# SchematicArtiom_fsch_v13.net
KiCad netlist of a schematic drawn in EAGLE
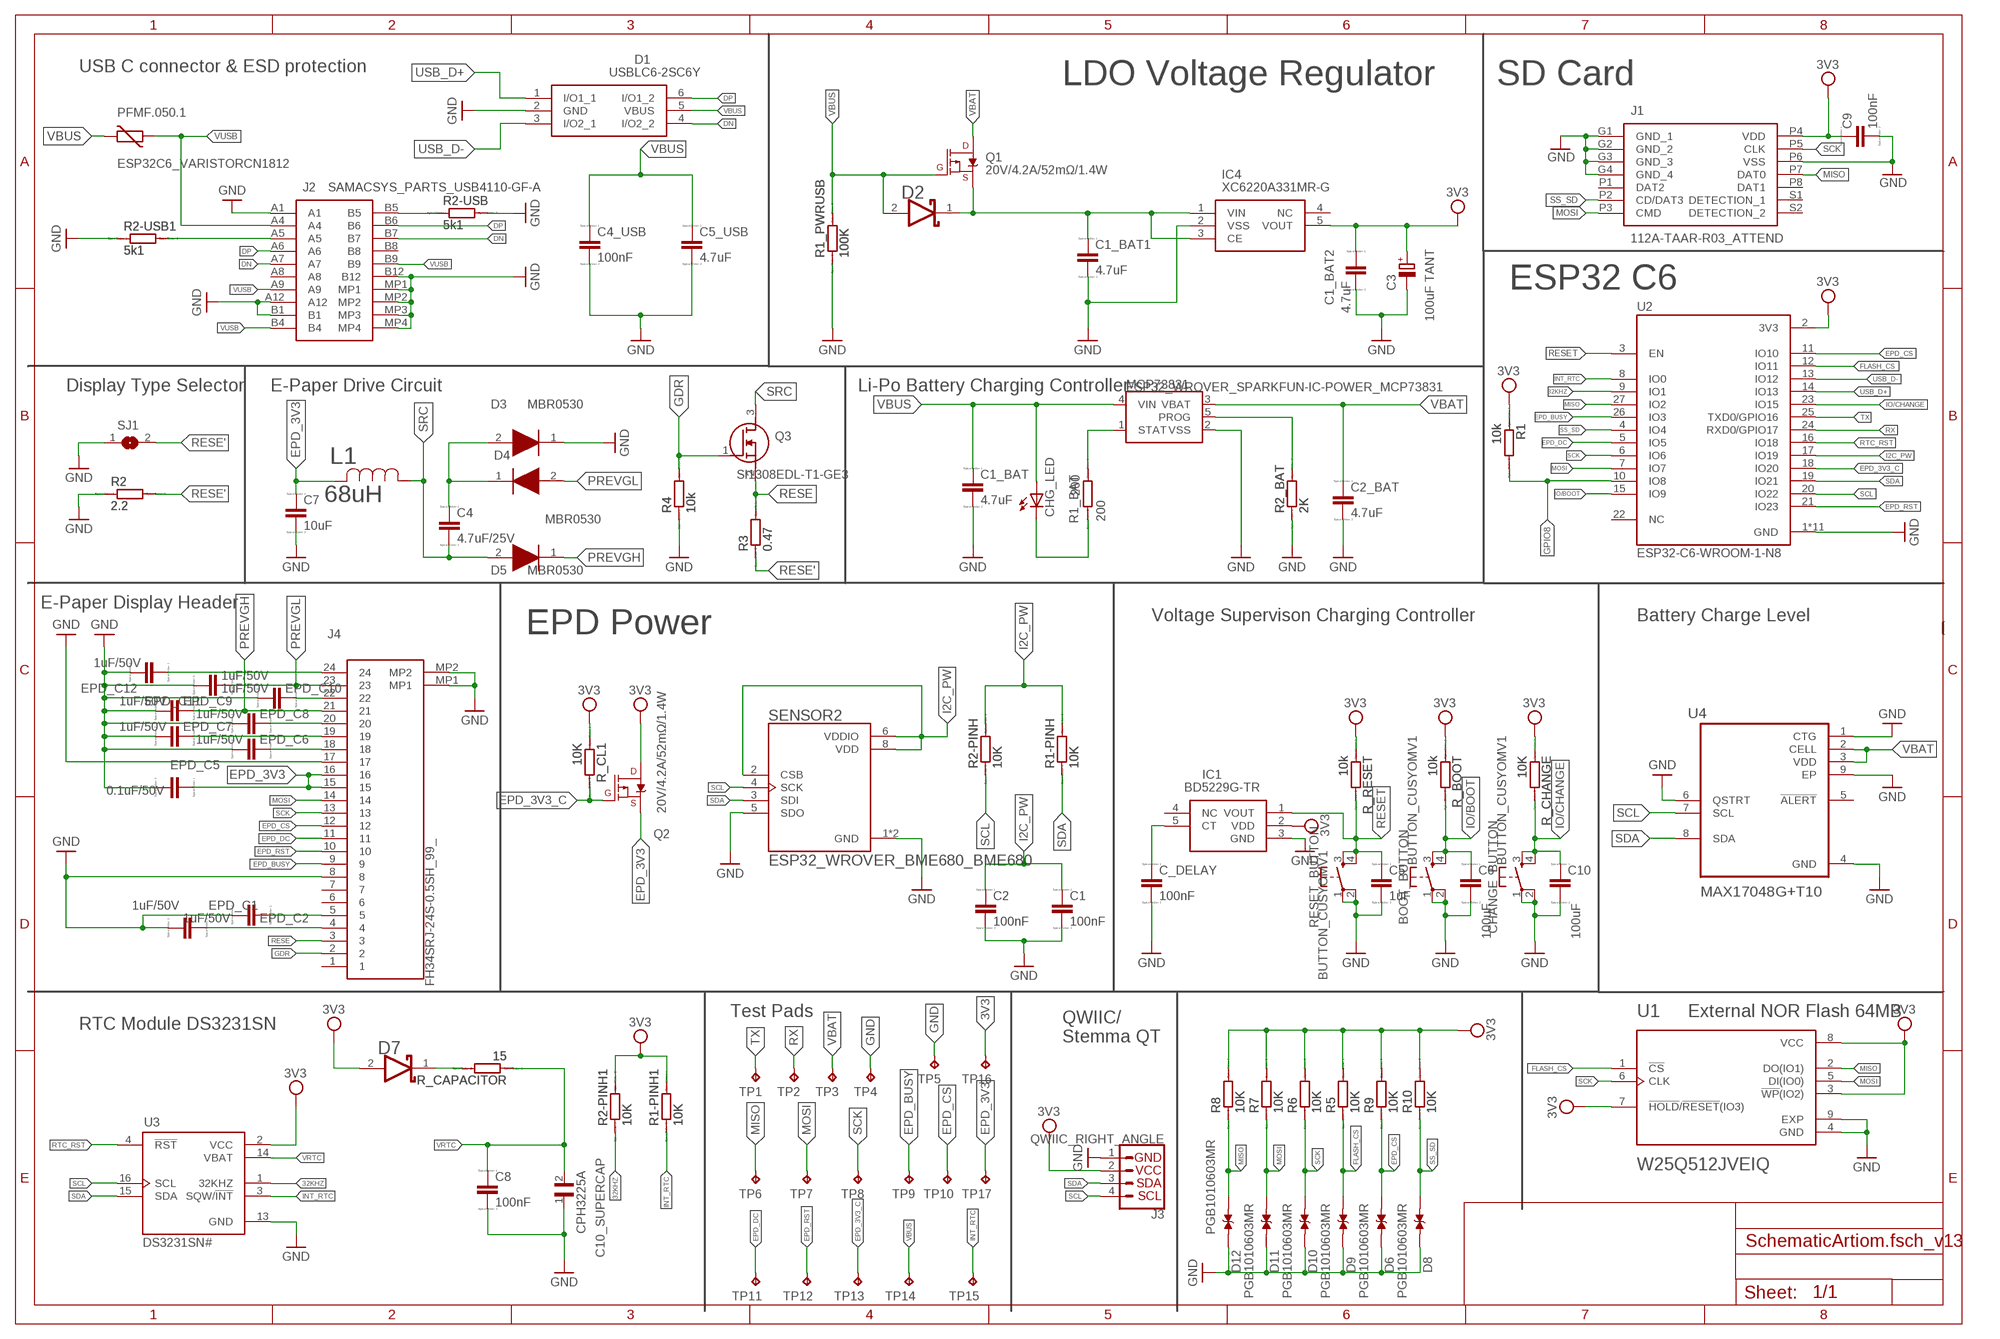
[diagram p0: schematic, sheet 1]

(export (version "E")
  (design (tool "Eeschema 10.0.6"))
  (components
    (comp (ref "BOOT_BUTTON")
      (value "BUTTON_CUSYOMV1")
      (footprint "eagle-import:MYBUTTON")
      (libsource (lib "eagle-import") (part "BUTTON_CUSYOMV1"))
    )
    (comp (ref "C1")
      (value "100nF")
      (footprint "eagle-import:ESP32_WROVER_EAGLE-LTSPICE_C0402")
      (libsource (lib "eagle-import") (part "ESP32_WROVER_EAGLE-LTSPICE_CC0402"))
    )
    (comp (ref "C1_BAT")
      (value "4.7uF")
      (footprint "eagle-import:ESP32_WROVER_EAGLE-LTSPICE_C0402")
      (libsource (lib "eagle-import") (part "ESP32_WROVER_EAGLE-LTSPICE_CC0402"))
    )
    (comp (ref "C1_BAT1")
      (value "4.7uF")
      (footprint "eagle-import:EAGLE-LTSPICE_C0402")
      (libsource (lib "eagle-import") (part "EAGLE-LTSPICE_CC0402"))
    )
    (comp (ref "C1_BAT2")
      (value "4.7uF")
      (footprint "eagle-import:EAGLE-LTSPICE_C0402")
      (libsource (lib "eagle-import") (part "EAGLE-LTSPICE_CC0402"))
    )
    (comp (ref "C2")
      (value "100nF")
      (footprint "eagle-import:ESP32_WROVER_EAGLE-LTSPICE_C0402")
      (libsource (lib "eagle-import") (part "ESP32_WROVER_EAGLE-LTSPICE_CC0402"))
    )
    (comp (ref "C2_BAT")
      (value "4.7uF")
      (footprint "eagle-import:ESP32_WROVER_EAGLE-LTSPICE_C0402")
      (libsource (lib "eagle-import") (part "ESP32_WROVER_EAGLE-LTSPICE_CC0402"))
    )
    (comp (ref "C3")
      (value "100uF TANT")
      (footprint "eagle-import:RCL_CT3528")
      (libsource (lib "eagle-import") (part "RCL_CPOL-EUCT3528"))
    )
    (comp (ref "C4")
      (value "4.7uF/25V")
      (footprint "eagle-import:ESP32_WROVER_EAGLE-LTSPICE_C0402")
      (libsource (lib "eagle-import") (part "ESP32_WROVER_EAGLE-LTSPICE_CC0402"))
    )
    (comp (ref "C4_USB")
      (value "100nF")
      (footprint "eagle-import:ESP32_WROVER_EAGLE-LTSPICE_C0402")
      (libsource (lib "eagle-import") (part "ESP32_WROVER_EAGLE-LTSPICE_CC0402"))
    )
    (comp (ref "C5")
      (value "1uF")
      (footprint "eagle-import:ESP32_WROVER_EAGLE-LTSPICE_C0402")
      (libsource (lib "eagle-import") (part "ESP32_WROVER_EAGLE-LTSPICE_CC0402"))
    )
    (comp (ref "C5_USB")
      (value "4.7uF")
      (footprint "eagle-import:ESP32_WROVER_EAGLE-LTSPICE_C0402")
      (libsource (lib "eagle-import") (part "ESP32_WROVER_EAGLE-LTSPICE_CC0402"))
    )
    (comp (ref "C6")
      (value "100uF")
      (footprint "eagle-import:ESP32_WROVER_EAGLE-LTSPICE_C0402")
      (libsource (lib "eagle-import") (part "ESP32_WROVER_EAGLE-LTSPICE_CC0402"))
    )
    (comp (ref "C7")
      (value "10uF")
      (footprint "eagle-import:ESP32_WROVER_EAGLE-LTSPICE_C0402")
      (libsource (lib "eagle-import") (part "ESP32_WROVER_EAGLE-LTSPICE_CC0402"))
    )
    (comp (ref "C8")
      (value "100nF")
      (footprint "eagle-import:ESP32_WROVER_EAGLE-LTSPICE_C0402")
      (libsource (lib "eagle-import") (part "ESP32_WROVER_EAGLE-LTSPICE_CC0402"))
    )
    (comp (ref "C9")
      (value "100nF")
      (footprint "eagle-import:EAGLE-LTSPICE_C0402")
      (libsource (lib "eagle-import") (part "EAGLE-LTSPICE_CC0402"))
    )
    (comp (ref "C10")
      (value "100uF")
      (footprint "eagle-import:ESP32_WROVER_EAGLE-LTSPICE_C0402")
      (libsource (lib "eagle-import") (part "ESP32_WROVER_EAGLE-LTSPICE_CC0402"))
    )
    (comp (ref "C10_SUPERCAP")
      (value "CPH3225A")
      (footprint "eagle-import:CAPCP3225X100N")
      (fields (field (name "MF") "Seiko Instruments"))
      (libsource (lib "eagle-import") (part "CPH3225A"))
    )
    (comp (ref "CHANGE_BUTTON")
      (value "BUTTON_CUSYOMV1")
      (footprint "eagle-import:MYBUTTON")
      (libsource (lib "eagle-import") (part "BUTTON_CUSYOMV1"))
    )
    (comp (ref "CHG_LED")
      (value "ADAFRUIT_LEDCHIP-LED0603")
      (footprint "eagle-import:ADAFRUIT_CHIP-LED0603")
      (libsource (lib "eagle-import") (part "ADAFRUIT_LEDCHIP-LED0603"))
    )
    (comp (ref "C_DELAY")
      (value "100nF")
      (footprint "eagle-import:EAGLE-LTSPICE_C0402")
      (libsource (lib "eagle-import") (part "EAGLE-LTSPICE_CC0402"))
    )
    (comp (ref "D1")
      (value "USBLC6-2SC6Y")
      (footprint "eagle-import:SOT95P280X145-6N")
      (fields (field (name "MF") "STMicroelectronics"))
      (libsource (lib "eagle-import") (part "USBLC6-2SC6Y"))
    )
    (comp (ref "D2")
      (value "ESP32_WROVER_AVX---SD0805S020S1R0_AVX_SD0805S020S1R0_0_0AVX_SD0805S020S1R0_0_0")
      (footprint "eagle-import:ESP32_WROVER_AVX---SD0805S020S1R0_AVX_SD0805S020S1R0_0")
      (fields
        (field (name "DIGIKEY_PART_NUMBER") "478-7800-1-ND")
        (field (name "MF") "AVX")
        (field (name "MOUSER_PART_NUMBER") "581-SD0805S020S1R0")
      )
      (libsource (lib "eagle-import") (part "ESP32_WROVER_AVX---SD0805S020S1R0_AVX_SD0805S020S1R0_0_0AVX_SD0805S020S1R0_0_0"))
    )
    (comp (ref "D3")
      (value "MBR0530")
      (footprint "eagle-import:SOD3716X135N")
      (fields (field (name "MF") "ON Semiconductor"))
      (libsource (lib "eagle-import") (part "MBR0530"))
    )
    (comp (ref "D4")
      (value "MBR0530")
      (footprint "eagle-import:SOD3716X135N")
      (fields (field (name "MF") "ON Semiconductor"))
      (libsource (lib "eagle-import") (part "MBR0530"))
    )
    (comp (ref "D5")
      (value "MBR0530")
      (footprint "eagle-import:SOD3716X135N")
      (fields (field (name "MF") "ON Semiconductor"))
      (libsource (lib "eagle-import") (part "MBR0530"))
    )
    (comp (ref "D6")
      (value "PGB1010603MR")
      (footprint "eagle-import:DIOC1608X36N")
      (fields (field (name "MF") "Littelfuse Inc."))
      (libsource (lib "eagle-import") (part "PGB1010603MR"))
    )
    (comp (ref "D7")
      (value "ESP32_WROVER_AVX---SD0805S020S1R0_AVX_SD0805S020S1R0_0_0AVX_SD0805S020S1R0_0_0")
      (footprint "eagle-import:ESP32_WROVER_AVX---SD0805S020S1R0_AVX_SD0805S020S1R0_0")
      (fields
        (field (name "DIGIKEY_PART_NUMBER") "478-7800-1-ND")
        (field (name "MF") "AVX")
        (field (name "MOUSER_PART_NUMBER") "581-SD0805S020S1R0")
      )
      (libsource (lib "eagle-import") (part "ESP32_WROVER_AVX---SD0805S020S1R0_AVX_SD0805S020S1R0_0_0AVX_SD0805S020S1R0_0_0"))
    )
    (comp (ref "D8")
      (value "PGB1010603MR")
      (footprint "eagle-import:DIOC1608X36N")
      (fields (field (name "MF") "Littelfuse Inc."))
      (libsource (lib "eagle-import") (part "PGB1010603MR"))
    )
    (comp (ref "D9")
      (value "PGB1010603MR")
      (footprint "eagle-import:DIOC1608X36N")
      (fields (field (name "MF") "Littelfuse Inc."))
      (libsource (lib "eagle-import") (part "PGB1010603MR"))
    )
    (comp (ref "D10")
      (value "PGB1010603MR")
      (footprint "eagle-import:DIOC1608X36N")
      (fields (field (name "MF") "Littelfuse Inc."))
      (libsource (lib "eagle-import") (part "PGB1010603MR"))
    )
    (comp (ref "D11")
      (value "PGB1010603MR")
      (footprint "eagle-import:DIOC1608X36N")
      (fields (field (name "MF") "Littelfuse Inc."))
      (libsource (lib "eagle-import") (part "PGB1010603MR"))
    )
    (comp (ref "D12")
      (value "PGB1010603MR")
      (footprint "eagle-import:DIOC1608X36N")
      (fields (field (name "MF") "Littelfuse Inc."))
      (libsource (lib "eagle-import") (part "PGB1010603MR"))
    )
    (comp (ref "EPD_C1")
      (value "1uF/50V")
      (footprint "eagle-import:ESP32_WROVER_EAGLE-LTSPICE_C0402")
      (libsource (lib "eagle-import") (part "ESP32_WROVER_EAGLE-LTSPICE_CC0402"))
    )
    (comp (ref "EPD_C2")
      (value "1uF/50V")
      (footprint "eagle-import:ESP32_WROVER_EAGLE-LTSPICE_C0402")
      (libsource (lib "eagle-import") (part "ESP32_WROVER_EAGLE-LTSPICE_CC0402"))
    )
    (comp (ref "EPD_C5")
      (value "0.1uF/50V")
      (footprint "eagle-import:ESP32_WROVER_EAGLE-LTSPICE_C0402")
      (libsource (lib "eagle-import") (part "ESP32_WROVER_EAGLE-LTSPICE_CC0402"))
    )
    (comp (ref "EPD_C6")
      (value "1uF/50V")
      (footprint "eagle-import:ESP32_WROVER_EAGLE-LTSPICE_C0402")
      (libsource (lib "eagle-import") (part "ESP32_WROVER_EAGLE-LTSPICE_CC0402"))
    )
    (comp (ref "EPD_C7")
      (value "1uF/50V")
      (footprint "eagle-import:ESP32_WROVER_EAGLE-LTSPICE_C0402")
      (libsource (lib "eagle-import") (part "ESP32_WROVER_EAGLE-LTSPICE_CC0402"))
    )
    (comp (ref "EPD_C8")
      (value "1uF/50V")
      (footprint "eagle-import:ESP32_WROVER_EAGLE-LTSPICE_C0402")
      (libsource (lib "eagle-import") (part "ESP32_WROVER_EAGLE-LTSPICE_CC0402"))
    )
    (comp (ref "EPD_C9")
      (value "1uF/50V")
      (footprint "eagle-import:ESP32_WROVER_EAGLE-LTSPICE_C0402")
      (libsource (lib "eagle-import") (part "ESP32_WROVER_EAGLE-LTSPICE_CC0402"))
    )
    (comp (ref "EPD_C10")
      (value "1uF/50V")
      (footprint "eagle-import:ESP32_WROVER_EAGLE-LTSPICE_C0402")
      (libsource (lib "eagle-import") (part "ESP32_WROVER_EAGLE-LTSPICE_CC0402"))
    )
    (comp (ref "EPD_C11")
      (value "1uF/50V")
      (footprint "eagle-import:ESP32_WROVER_EAGLE-LTSPICE_C0402")
      (libsource (lib "eagle-import") (part "ESP32_WROVER_EAGLE-LTSPICE_CC0402"))
    )
    (comp (ref "EPD_C12")
      (value "1uF/50V")
      (footprint "eagle-import:ESP32_WROVER_EAGLE-LTSPICE_C0402")
      (libsource (lib "eagle-import") (part "ESP32_WROVER_EAGLE-LTSPICE_CC0402"))
    )
    (comp (ref "IC1")
      (value "BD5229G-TR")
      (footprint "eagle-import:SOT95P280X125-5N")
      (fields (field (name "MOUSER_PART_NUMBER") "755-BD5229G-TR"))
      (libsource (lib "eagle-import") (part "BD5229G-TR"))
    )
    (comp (ref "IC4")
      (value "XC6220A331MR-G")
      (footprint "eagle-import:SOT95P280X120-5N")
      (fields (field (name "MOUSER_PART_NUMBER") "865-XC6220A331MR-G"))
      (libsource (lib "eagle-import") (part "XC6220A331MR-G"))
    )
    (comp (ref "J1")
      (value "112A-TAAR-R03_ATTEND")
      (footprint "eagle-import:112ATAARR03ATTEND")
      (fields (field (name "MANUFACTURER_PART_NUMBER") "112A-TAAR-R03 ATTEND"))
      (libsource (lib "eagle-import") (part "112A-TAAR-R03_ATTEND"))
    )
    (comp (ref "J2")
      (value "SAMACSYS_PARTS_USB4110-GF-A")
      (footprint "eagle-import:SAMACSYS_PARTS_USB4110GFA")
      (fields
        (field (name "MANUFACTURER_PART_NUMBER") "USB4110-GF-A")
        (field (name "MOUSER_PART_NUMBER") "640-USB4110-GF-A")
      )
      (libsource (lib "eagle-import") (part "SAMACSYS_PARTS_USB4110-GF-A"))
    )
    (comp (ref "J3")
      (value "QWIIC_RIGHT_ANGLE")
      (footprint "eagle-import:JST04_1MM_RA")
      (libsource (lib "eagle-import") (part "QWIIC_CONNECTORJS-1MM"))
    )
    (comp (ref "J4")
      (value "FH34SRJ-24S-0.5SH_99_")
      (footprint "eagle-import:FH34SRJ24S05SH99")
      (fields
        (field (name "MANUFACTURER_PART_NUMBER") "FH34SRJ-24S-0.5SH(99)")
        (field (name "MOUSER_PART_NUMBER") "798-FH34SRJ24S05SH99")
      )
      (libsource (lib "eagle-import") (part "FH34SRJ-24S-0.5SH_99_"))
    )
    (comp (ref "L1")
      (value "68uH")
      (footprint "eagle-import:IND_4828-WE-TPC_WRE")
      (fields
        (field (name "MANUFACTURER_PART_NUMBER") "744043680")
        (field (name "COPYRIGHT") "Copyright (C) 2024 Ultra Librarian. All rights reserved.")
      )
      (libsource (lib "eagle-import") (part "744043680IND_4828-WE-TPC_WRE"))
    )
    (comp (ref "MCP73831")
      (value "ESP32_WROVER_SPARKFUN-IC-POWER_MCP73831")
      (footprint "eagle-import:ESP32_WROVER_SPARKFUN-IC-POWER_SOT23-5")
      (libsource (lib "eagle-import") (part "ESP32_WROVER_SPARKFUN-IC-POWER_MCP73831"))
    )
    (comp (ref "PFMF.050.1")
      (value "ESP32C6_VARISTORCN1812")
      (footprint "eagle-import:ESP32C6_VARISTOR_CT_CN1812")
      (libsource (lib "eagle-import") (part "ESP32C6_VARISTORCN1812"))
    )
    (comp (ref "Q1")
      (value "20V/4.2A/52mΩ/1.4W")
      (footprint "eagle-import:ESP32_WROVER_SPARKFUN-DISCRETESEMI_SOT23-3")
      (libsource (lib "eagle-import") (part "ESP32_WROVER_SPARKFUN-DISCRETESEMI_MOSFET_PCH-DMG2305UX-7"))
    )
    (comp (ref "Q2")
      (value "20V/4.2A/52mΩ/1.4W")
      (footprint "eagle-import:ESP32_WROVER_SPARKFUN-DISCRETESEMI_SOT23-3")
      (libsource (lib "eagle-import") (part "ESP32_WROVER_SPARKFUN-DISCRETESEMI_MOSFET_PCH-DMG2305UX-7"))
    )
    (comp (ref "Q3")
      (value "SI1308EDL-T1-GE3")
      (footprint "eagle-import:SOT65P210X110-3N")
      (fields (field (name "MF") "Vishay Siliconix"))
      (libsource (lib "eagle-import") (part "SI1308EDL-T1-GE3"))
    )
    (comp (ref "R1")
      (value "10k")
      (footprint "eagle-import:ESP32_WROVER_EAGLE-LTSPICE_R0402")
      (libsource (lib "eagle-import") (part "ESP32_WROVER_EAGLE-LTSPICE_RR0402"))
    )
    (comp (ref "R1-PINH")
      (value "10K")
      (footprint "eagle-import:ESP32_WROVER_EAGLE-LTSPICE_R0402")
      (libsource (lib "eagle-import") (part "ESP32_WROVER_EAGLE-LTSPICE_RR0402"))
    )
    (comp (ref "R1-PINH1")
      (value "10K")
      (footprint "eagle-import:ESP32_WROVER_EAGLE-LTSPICE_R0402")
      (libsource (lib "eagle-import") (part "ESP32_WROVER_EAGLE-LTSPICE_RR0402"))
    )
    (comp (ref "R1_BAT")
      (value "200")
      (footprint "eagle-import:ESP32_WROVER_EAGLE-LTSPICE_R0402")
      (libsource (lib "eagle-import") (part "ESP32_WROVER_EAGLE-LTSPICE_RR0402"))
    )
    (comp (ref "R1_PWRUSB")
      (value "100K")
      (footprint "eagle-import:ESP32_WROVER_EAGLE-LTSPICE_R0402")
      (libsource (lib "eagle-import") (part "ESP32_WROVER_EAGLE-LTSPICE_RR0402"))
    )
    (comp (ref "R2")
      (value "2.2")
      (footprint "eagle-import:ESP32_WROVER_EAGLE-LTSPICE_R0402")
      (libsource (lib "eagle-import") (part "ESP32_WROVER_EAGLE-LTSPICE_RR0402"))
    )
    (comp (ref "R2-PINH")
      (value "10K")
      (footprint "eagle-import:ESP32_WROVER_EAGLE-LTSPICE_R0402")
      (libsource (lib "eagle-import") (part "ESP32_WROVER_EAGLE-LTSPICE_RR0402"))
    )
    (comp (ref "R2-PINH1")
      (value "10K")
      (footprint "eagle-import:ESP32_WROVER_EAGLE-LTSPICE_R0402")
      (libsource (lib "eagle-import") (part "ESP32_WROVER_EAGLE-LTSPICE_RR0402"))
    )
    (comp (ref "R2-USB")
      (value "5k1")
      (footprint "eagle-import:ESP32_WROVER_EAGLE-LTSPICE_R0402")
      (libsource (lib "eagle-import") (part "ESP32_WROVER_EAGLE-LTSPICE_RR0402"))
    )
    (comp (ref "R2-USB1")
      (value "5k1")
      (footprint "eagle-import:ESP32_WROVER_EAGLE-LTSPICE_R0402")
      (libsource (lib "eagle-import") (part "ESP32_WROVER_EAGLE-LTSPICE_RR0402"))
    )
    (comp (ref "R2_BAT")
      (value "2K")
      (footprint "eagle-import:ESP32_WROVER_EAGLE-LTSPICE_R0402")
      (libsource (lib "eagle-import") (part "ESP32_WROVER_EAGLE-LTSPICE_RR0402"))
    )
    (comp (ref "R3")
      (value "0.47")
      (footprint "eagle-import:ESP32_WROVER_EAGLE-LTSPICE_R0402")
      (libsource (lib "eagle-import") (part "ESP32_WROVER_EAGLE-LTSPICE_RR0402"))
    )
    (comp (ref "R4")
      (value "10k")
      (footprint "eagle-import:ESP32_WROVER_EAGLE-LTSPICE_R0402")
      (libsource (lib "eagle-import") (part "ESP32_WROVER_EAGLE-LTSPICE_RR0402"))
    )
    (comp (ref "R5")
      (value "10K")
      (footprint "eagle-import:ESP32_WROVER_EAGLE-LTSPICE_R0402")
      (libsource (lib "eagle-import") (part "ESP32_WROVER_EAGLE-LTSPICE_RR0402"))
    )
    (comp (ref "R6")
      (value "10K")
      (footprint "eagle-import:ESP32_WROVER_EAGLE-LTSPICE_R0402")
      (libsource (lib "eagle-import") (part "ESP32_WROVER_EAGLE-LTSPICE_RR0402"))
    )
    (comp (ref "R7")
      (value "10K")
      (footprint "eagle-import:ESP32_WROVER_EAGLE-LTSPICE_R0402")
      (libsource (lib "eagle-import") (part "ESP32_WROVER_EAGLE-LTSPICE_RR0402"))
    )
    (comp (ref "R8")
      (value "10K")
      (footprint "eagle-import:ESP32_WROVER_EAGLE-LTSPICE_R0402")
      (libsource (lib "eagle-import") (part "ESP32_WROVER_EAGLE-LTSPICE_RR0402"))
    )
    (comp (ref "R9")
      (value "10K")
      (footprint "eagle-import:ESP32_WROVER_EAGLE-LTSPICE_R0402")
      (libsource (lib "eagle-import") (part "ESP32_WROVER_EAGLE-LTSPICE_RR0402"))
    )
    (comp (ref "R10")
      (value "10K")
      (footprint "eagle-import:ESP32_WROVER_EAGLE-LTSPICE_R0402")
      (libsource (lib "eagle-import") (part "ESP32_WROVER_EAGLE-LTSPICE_RR0402"))
    )
    (comp (ref "RESET_BUTTON")
      (value "BUTTON_CUSYOMV1")
      (footprint "eagle-import:MYBUTTON")
      (libsource (lib "eagle-import") (part "BUTTON_CUSYOMV1"))
    )
    (comp (ref "R_BOOT")
      (value "10k")
      (footprint "eagle-import:ESP32_WROVER_EAGLE-LTSPICE_R0402")
      (libsource (lib "eagle-import") (part "ESP32_WROVER_EAGLE-LTSPICE_RR0402"))
    )
    (comp (ref "R_CAPACITOR")
      (value "15")
      (footprint "eagle-import:ESP32_WROVER_EAGLE-LTSPICE_R0402")
      (libsource (lib "eagle-import") (part "ESP32_WROVER_EAGLE-LTSPICE_RR0402"))
    )
    (comp (ref "R_CHANGE")
      (value "10K")
      (footprint "eagle-import:ESP32_WROVER_EAGLE-LTSPICE_R0402")
      (libsource (lib "eagle-import") (part "ESP32_WROVER_EAGLE-LTSPICE_RR0402"))
    )
    (comp (ref "R_CL1")
      (value "10K")
      (footprint "eagle-import:ESP32_WROVER_EAGLE-LTSPICE_R0402")
      (libsource (lib "eagle-import") (part "ESP32_WROVER_EAGLE-LTSPICE_RR0402"))
    )
    (comp (ref "R_RESET")
      (value "10k")
      (footprint "eagle-import:ESP32_WROVER_EAGLE-LTSPICE_R0402")
      (libsource (lib "eagle-import") (part "ESP32_WROVER_EAGLE-LTSPICE_RR0402"))
    )
    (comp (ref "SENSOR2")
      (value "ESP32_WROVER_BME680_BME680")
      (footprint "eagle-import:ESP32_WROVER_BME680_PSON80P300X300X100-8N")
      (fields (field (name "MF") "Bosch Sensortec") (field (name "MP") "BME680"))
      (libsource (lib "eagle-import") (part "ESP32_WROVER_BME680_BME680"))
    )
    (comp (ref "SJ1") (value "SJ") (footprint "eagle-import:SJ") (libsource (lib "eagle-import") (part "SJ")))
    (comp (ref "TP1")
      (value "TPTP20R")
      (footprint "eagle-import:TP20R")
      (libsource (lib "eagle-import") (part "TPTP20R"))
    )
    (comp (ref "TP2")
      (value "TPTP20R")
      (footprint "eagle-import:TP20R")
      (libsource (lib "eagle-import") (part "TPTP20R"))
    )
    (comp (ref "TP3")
      (value "TPTP20R")
      (footprint "eagle-import:TP20R")
      (libsource (lib "eagle-import") (part "TPTP20R"))
    )
    (comp (ref "TP4")
      (value "TPTP20R")
      (footprint "eagle-import:TP20R")
      (libsource (lib "eagle-import") (part "TPTP20R"))
    )
    (comp (ref "TP5")
      (value "TPTP20R")
      (footprint "eagle-import:TP20R")
      (libsource (lib "eagle-import") (part "TPTP20R"))
    )
    (comp (ref "TP6")
      (value "TPTP20R")
      (footprint "eagle-import:TP20R")
      (libsource (lib "eagle-import") (part "TPTP20R"))
    )
    (comp (ref "TP7")
      (value "TPTP20R")
      (footprint "eagle-import:TP20R")
      (libsource (lib "eagle-import") (part "TPTP20R"))
    )
    (comp (ref "TP8")
      (value "TPTP20R")
      (footprint "eagle-import:TP20R")
      (libsource (lib "eagle-import") (part "TPTP20R"))
    )
    (comp (ref "TP9")
      (value "TPTP20R")
      (footprint "eagle-import:TP20R")
      (libsource (lib "eagle-import") (part "TPTP20R"))
    )
    (comp (ref "TP10")
      (value "TPTP20R")
      (footprint "eagle-import:TP20R")
      (libsource (lib "eagle-import") (part "TPTP20R"))
    )
    (comp (ref "TP11")
      (value "TPTP20R")
      (footprint "eagle-import:TP20R")
      (libsource (lib "eagle-import") (part "TPTP20R"))
    )
    (comp (ref "TP12")
      (value "TPTP20R")
      (footprint "eagle-import:TP20R")
      (libsource (lib "eagle-import") (part "TPTP20R"))
    )
    (comp (ref "TP13")
      (value "TPTP20R")
      (footprint "eagle-import:TP20R")
      (libsource (lib "eagle-import") (part "TPTP20R"))
    )
    (comp (ref "TP14")
      (value "TPTP20R")
      (footprint "eagle-import:TP20R")
      (libsource (lib "eagle-import") (part "TPTP20R"))
    )
    (comp (ref "TP15")
      (value "TPTP20R")
      (footprint "eagle-import:TP20R")
      (libsource (lib "eagle-import") (part "TPTP20R"))
    )
    (comp (ref "TP16")
      (value "TPTP20R")
      (footprint "eagle-import:TP20R")
      (libsource (lib "eagle-import") (part "TPTP20R"))
    )
    (comp (ref "TP17")
      (value "TPTP20R")
      (footprint "eagle-import:TP20R")
      (libsource (lib "eagle-import") (part "TPTP20R"))
    )
    (comp (ref "U1")
      (value "W25Q512JVEIQ")
      (footprint "eagle-import:SON127P600X800X80-9N")
      (fields (field (name "MF") "Winbond Electronics"))
      (libsource (lib "eagle-import") (part "W25Q512JVEIQ"))
    )
    (comp (ref "U2")
      (value "ESP32-C6-WROOM-1-N8")
      (footprint "eagle-import:XCVR_ESP32-C6-WROOM-1-N8")
      (fields (field (name "MF") "Espressif Systems"))
      (libsource (lib "eagle-import") (part "ESP32-C6-WROOM-1-N8"))
    )
    (comp (ref "U3")
      (value "DS3231SN#")
      (footprint "eagle-import:SOIC127P1032X265-16N")
      (fields (field (name "MF") "Analog Devices"))
      (libsource (lib "eagle-import") (part "DS3231SN#"))
    )
    (comp (ref "U4")
      (value "MAX17048G+T10")
      (footprint "eagle-import:SON50P200X200X80-9N")
      (fields (field (name "MF") "Analog Devices"))
      (libsource (lib "eagle-import") (part "MAX17048G+T10"))
    )
  )
  (nets
    (net (code "1") (name "3V3") (class "Default")
      (node (ref "C1_BAT2") (pin "1") (pinfunction "1_1") (pintype "passive"))
      (node (ref "C3") (pin "+") (pinfunction "+_+") (pintype "passive"))
      (node (ref "C9") (pin "1") (pinfunction "1_1") (pintype "passive"))
      (node (ref "D7") (pin "2") (pinfunction "ANODE_2") (pintype "bidirectional"))
      (node (ref "IC1") (pin "2") (pinfunction "VDD_2") (pintype "bidirectional"))
      (node (ref "IC4") (pin "5") (pinfunction "VOUT_5") (pintype "bidirectional"))
      (node (ref "J1") (pin "P4") (pinfunction "VDD_P4") (pintype "bidirectional"))
      (node (ref "J3") (pin "2") (pinfunction "2_2") (pintype "power_in"))
      (node (ref "Q2") (pin "3") (pinfunction "D_3") (pintype "bidirectional"))
      (node (ref "R1") (pin "1") (pinfunction "1_1") (pintype "passive"))
      (node (ref "R1-PINH1") (pin "2") (pinfunction "2_2") (pintype "passive"))
      (node (ref "R10") (pin "2") (pinfunction "2_2") (pintype "passive"))
      (node (ref "R2-PINH1") (pin "2") (pinfunction "2_2") (pintype "passive"))
      (node (ref "R5") (pin "2") (pinfunction "2_2") (pintype "passive"))
      (node (ref "R6") (pin "2") (pinfunction "2_2") (pintype "passive"))
      (node (ref "R7") (pin "2") (pinfunction "2_2") (pintype "passive"))
      (node (ref "R8") (pin "2") (pinfunction "2_2") (pintype "passive"))
      (node (ref "R9") (pin "2") (pinfunction "2_2") (pintype "passive"))
      (node (ref "R_BOOT") (pin "1") (pinfunction "1_1") (pintype "passive"))
      (node (ref "R_CHANGE") (pin "1") (pinfunction "1_1") (pintype "passive"))
      (node (ref "R_CL1") (pin "1") (pinfunction "1_1") (pintype "passive"))
      (node (ref "R_RESET") (pin "1") (pinfunction "1_1") (pintype "passive"))
      (node (ref "TP16") (pin "TP") (pinfunction "TP_TP") (pintype "input"))
      (node (ref "U1") (pin "3") (pinfunction "~{WP}(IO2)_3") (pintype "bidirectional"))
      (node (ref "U1") (pin "7") (pinfunction "~{HOLD}/~{RESET}(IO3)_7") (pintype "bidirectional"))
      (node (ref "U1") (pin "8") (pinfunction "VCC_8") (pintype "power_in"))
      (node (ref "U2") (pin "2") (pinfunction "3V3_2") (pintype "power_in"))
      (node (ref "U3") (pin "2") (pinfunction "VCC_2") (pintype "power_in"))
    )
    (net (code "2") (name "32KHZ") (class "Default")
      (node (ref "R2-PINH1") (pin "1") (pinfunction "1_1") (pintype "passive"))
      (node (ref "U2") (pin "9") (pinfunction "IO1_9") (pintype "bidirectional"))
      (node (ref "U3") (pin "1") (pinfunction "32KHZ_1") (pintype "output"))
    )
    (net (code "3") (name "DN") (class "Default")
      (node (ref "D1") (pin "4") (pinfunction "I/O2_2_4") (pintype "bidirectional"))
      (node (ref "J2") (pin "A7") (pinfunction "A7_A7") (pintype "bidirectional"))
      (node (ref "J2") (pin "B7") (pinfunction "B7_B7") (pintype "bidirectional"))
    )
    (net (code "4") (name "DP") (class "Default")
      (node (ref "D1") (pin "6") (pinfunction "I/O1_2_6") (pintype "bidirectional"))
      (node (ref "J2") (pin "A6") (pinfunction "A6_A6") (pintype "bidirectional"))
      (node (ref "J2") (pin "B6") (pinfunction "B6_B6") (pintype "bidirectional"))
    )
    (net (code "5") (name "EPD_3V3") (class "Default")
      (node (ref "C7") (pin "1") (pinfunction "1_1") (pintype "passive"))
      (node (ref "EPD_C5") (pin "1") (pinfunction "1_1") (pintype "passive"))
      (node (ref "J4") (pin "15") (pinfunction "15_15") (pintype "bidirectional"))
      (node (ref "J4") (pin "16") (pinfunction "16_16") (pintype "bidirectional"))
      (node (ref "L1") (pin "2") (pinfunction "2_2") (pintype "passive"))
      (node (ref "Q2") (pin "2") (pinfunction "S_2") (pintype "bidirectional"))
      (node (ref "TP17") (pin "TP") (pinfunction "TP_TP") (pintype "input"))
    )
    (net (code "6") (name "EPD_3V3_C") (class "Default")
      (node (ref "Q2") (pin "1") (pinfunction "G_1") (pintype "bidirectional"))
      (node (ref "R_CL1") (pin "2") (pinfunction "2_2") (pintype "passive"))
      (node (ref "TP13") (pin "TP") (pinfunction "TP_TP") (pintype "input"))
      (node (ref "U2") (pin "18") (pinfunction "IO20_18") (pintype "bidirectional"))
    )
    (net (code "7") (name "EPD_BUSY") (class "Default")
      (node (ref "J4") (pin "9") (pinfunction "9_9") (pintype "bidirectional"))
      (node (ref "TP9") (pin "TP") (pinfunction "TP_TP") (pintype "input"))
      (node (ref "U2") (pin "26") (pinfunction "IO3_26") (pintype "bidirectional"))
    )
    (net (code "8") (name "EPD_CS") (class "Default")
      (node (ref "D6") (pin "2") (pinfunction "2_2") (pintype "passive"))
      (node (ref "J4") (pin "12") (pinfunction "12_12") (pintype "bidirectional"))
      (node (ref "R9") (pin "1") (pinfunction "1_1") (pintype "passive"))
      (node (ref "TP10") (pin "TP") (pinfunction "TP_TP") (pintype "input"))
      (node (ref "U2") (pin "11") (pinfunction "IO10_11") (pintype "bidirectional"))
    )
    (net (code "9") (name "EPD_DC") (class "Default")
      (node (ref "J4") (pin "11") (pinfunction "11_11") (pintype "bidirectional"))
      (node (ref "TP11") (pin "TP") (pinfunction "TP_TP") (pintype "input"))
      (node (ref "U2") (pin "5") (pinfunction "IO5_5") (pintype "bidirectional"))
    )
    (net (code "10") (name "EPD_RST") (class "Default")
      (node (ref "J4") (pin "10") (pinfunction "10_10") (pintype "bidirectional"))
      (node (ref "TP12") (pin "TP") (pinfunction "TP_TP") (pintype "input"))
      (node (ref "U2") (pin "21") (pinfunction "IO23_21") (pintype "bidirectional"))
    )
    (net (code "11") (name "FLASH_CS") (class "Default")
      (node (ref "D9") (pin "2") (pinfunction "2_2") (pintype "passive"))
      (node (ref "R5") (pin "1") (pinfunction "1_1") (pintype "passive"))
      (node (ref "U1") (pin "1") (pinfunction "~{CS}_1") (pintype "input"))
      (node (ref "U2") (pin "12") (pinfunction "IO11_12") (pintype "bidirectional"))
    )
    (net (code "12") (name "GDR") (class "Default")
      (node (ref "J4") (pin "2") (pinfunction "2_2") (pintype "bidirectional"))
      (node (ref "Q3") (pin "1") (pinfunction "G_1") (pintype "bidirectional"))
      (node (ref "R4") (pin "2") (pinfunction "2_2") (pintype "passive"))
    )
    (net (code "13") (name "GND") (class "Default")
      (node (ref "BOOT_BUTTON") (pin "1") (pinfunction "1_1") (pintype "passive"))
      (node (ref "BOOT_BUTTON") (pin "2") (pinfunction "2_2") (pintype "passive"))
      (node (ref "C1") (pin "2") (pinfunction "2_2") (pintype "passive"))
      (node (ref "C10") (pin "2") (pinfunction "2_2") (pintype "passive"))
      (node (ref "C10_SUPERCAP") (pin "1") (pinfunction "1_1") (pintype "passive"))
      (node (ref "C1_BAT") (pin "2") (pinfunction "2_2") (pintype "passive"))
      (node (ref "C1_BAT1") (pin "2") (pinfunction "2_2") (pintype "passive"))
      (node (ref "C1_BAT2") (pin "2") (pinfunction "2_2") (pintype "passive"))
      (node (ref "C2") (pin "2") (pinfunction "2_2") (pintype "passive"))
      (node (ref "C2_BAT") (pin "2") (pinfunction "2_2") (pintype "passive"))
      (node (ref "C3") (pin "-") (pinfunction "-_-") (pintype "passive"))
      (node (ref "C4_USB") (pin "2") (pinfunction "2_2") (pintype "passive"))
      (node (ref "C5") (pin "2") (pinfunction "2_2") (pintype "passive"))
      (node (ref "C5_USB") (pin "2") (pinfunction "2_2") (pintype "passive"))
      (node (ref "C6") (pin "2") (pinfunction "2_2") (pintype "passive"))
      (node (ref "C7") (pin "2") (pinfunction "2_2") (pintype "passive"))
      (node (ref "C8") (pin "2") (pinfunction "2_2") (pintype "passive"))
      (node (ref "C9") (pin "2") (pinfunction "2_2") (pintype "passive"))
      (node (ref "CHANGE_BUTTON") (pin "1") (pinfunction "1_1") (pintype "passive"))
      (node (ref "CHANGE_BUTTON") (pin "2") (pinfunction "2_2") (pintype "passive"))
      (node (ref "C_DELAY") (pin "2") (pinfunction "2_2") (pintype "passive"))
      (node (ref "D1") (pin "2") (pinfunction "GND_2") (pintype "bidirectional"))
      (node (ref "D10") (pin "1") (pinfunction "1_1") (pintype "passive"))
      (node (ref "D11") (pin "1") (pinfunction "1_1") (pintype "passive"))
      (node (ref "D12") (pin "1") (pinfunction "1_1") (pintype "passive"))
      (node (ref "D3") (pin "1") (pinfunction "K_1") (pintype "bidirectional"))
      (node (ref "D6") (pin "1") (pinfunction "1_1") (pintype "passive"))
      (node (ref "D8") (pin "1") (pinfunction "1_1") (pintype "passive"))
      (node (ref "D9") (pin "1") (pinfunction "1_1") (pintype "passive"))
      (node (ref "EPD_C1") (pin "2") (pinfunction "2_2") (pintype "passive"))
      (node (ref "EPD_C10") (pin "2") (pinfunction "2_2") (pintype "passive"))
      (node (ref "EPD_C11") (pin "2") (pinfunction "2_2") (pintype "passive"))
      (node (ref "EPD_C12") (pin "2") (pinfunction "2_2") (pintype "passive"))
      (node (ref "EPD_C2") (pin "2") (pinfunction "2_2") (pintype "passive"))
      (node (ref "EPD_C5") (pin "2") (pinfunction "2_2") (pintype "passive"))
      (node (ref "EPD_C6") (pin "2") (pinfunction "2_2") (pintype "passive"))
      (node (ref "EPD_C7") (pin "2") (pinfunction "2_2") (pintype "passive"))
      (node (ref "EPD_C8") (pin "2") (pinfunction "2_2") (pintype "passive"))
      (node (ref "EPD_C9") (pin "2") (pinfunction "2_2") (pintype "passive"))
      (node (ref "IC1") (pin "3") (pinfunction "GND_3") (pintype "bidirectional"))
      (node (ref "IC4") (pin "2") (pinfunction "VSS_2") (pintype "bidirectional"))
      (node (ref "J1") (pin "G1") (pinfunction "GND_1_G1") (pintype "bidirectional"))
      (node (ref "J1") (pin "G2") (pinfunction "GND_2_G2") (pintype "bidirectional"))
      (node (ref "J1") (pin "G3") (pinfunction "GND_3_G3") (pintype "bidirectional"))
      (node (ref "J1") (pin "G4") (pinfunction "GND_4_G4") (pintype "bidirectional"))
      (node (ref "J1") (pin "P6") (pinfunction "VSS_P6") (pintype "bidirectional"))
      (node (ref "J2") (pin "A1") (pinfunction "A1_A1") (pintype "bidirectional"))
      (node (ref "J2") (pin "A12") (pinfunction "A12_A12") (pintype "bidirectional"))
      (node (ref "J2") (pin "B1") (pinfunction "B1_B1") (pintype "bidirectional"))
      (node (ref "J2") (pin "B12") (pinfunction "B12_B12") (pintype "bidirectional"))
      (node (ref "J2") (pin "MP1") (pinfunction "MP1_MP1") (pintype "bidirectional"))
      (node (ref "J2") (pin "MP2") (pinfunction "MP2_MP2") (pintype "bidirectional"))
      (node (ref "J2") (pin "MP3") (pinfunction "MP3_MP3") (pintype "bidirectional"))
      (node (ref "J2") (pin "MP4") (pinfunction "MP4_MP4") (pintype "bidirectional"))
      (node (ref "J3") (pin "1") (pinfunction "1_1") (pintype "power_in"))
      (node (ref "J4") (pin "17") (pinfunction "17_17") (pintype "bidirectional"))
      (node (ref "J4") (pin "8") (pinfunction "8_8") (pintype "bidirectional"))
      (node (ref "J4") (pin "MP1") (pinfunction "MP1_MP1") (pintype "bidirectional"))
      (node (ref "J4") (pin "MP2") (pinfunction "MP2_MP2") (pintype "bidirectional"))
      (node (ref "MCP73831") (pin "2") (pinfunction "VSS_2") (pintype "power_in"))
      (node (ref "R1_PWRUSB") (pin "1") (pinfunction "1_1") (pintype "passive"))
      (node (ref "R2") (pin "1") (pinfunction "1_1") (pintype "passive"))
      (node (ref "R2-USB") (pin "2") (pinfunction "2_2") (pintype "passive"))
      (node (ref "R2-USB1") (pin "1") (pinfunction "1_1") (pintype "passive"))
      (node (ref "R2_BAT") (pin "1") (pinfunction "1_1") (pintype "passive"))
      (node (ref "R4") (pin "1") (pinfunction "1_1") (pintype "passive"))
      (node (ref "RESET_BUTTON") (pin "1") (pinfunction "1_1") (pintype "passive"))
      (node (ref "RESET_BUTTON") (pin "2") (pinfunction "2_2") (pintype "passive"))
      (node (ref "SENSOR2") (pin "1") (pinfunction "GND_1") (pintype "power_in"))
      (node (ref "SENSOR2") (pin "5") (pinfunction "SDO_5") (pintype "bidirectional"))
      (node (ref "SENSOR2") (pin "7") (pinfunction "GND_7") (pintype "power_in"))
      (node (ref "SJ1") (pin "1") (pinfunction "1_1") (pintype "passive"))
      (node (ref "TP4") (pin "TP") (pinfunction "TP_TP") (pintype "input"))
      (node (ref "TP5") (pin "TP") (pinfunction "TP_TP") (pintype "input"))
      (node (ref "U1") (pin "4") (pinfunction "GND_4") (pintype "power_in"))
      (node (ref "U1") (pin "9") (pinfunction "EXP_9") (pintype "passive"))
      (node (ref "U2") (pin "1") (pinfunction "GND_1") (pintype "power_in"))
      (node (ref "U2") (pin "28") (pinfunction "GND_28") (pintype "power_in"))
      (node (ref "U2") (pin "29_1") (pinfunction "GND_29_1") (pintype "power_in"))
      (node (ref "U2") (pin "29_2") (pinfunction "GND_29_2") (pintype "power_in"))
      (node (ref "U2") (pin "29_3") (pinfunction "GND_29_3") (pintype "power_in"))
      (node (ref "U2") (pin "29_4") (pinfunction "GND_29_4") (pintype "power_in"))
      (node (ref "U2") (pin "29_5") (pinfunction "GND_29_5") (pintype "power_in"))
      (node (ref "U2") (pin "29_6") (pinfunction "GND_29_6") (pintype "power_in"))
      (node (ref "U2") (pin "29_7") (pinfunction "GND_29_7") (pintype "power_in"))
      (node (ref "U2") (pin "29_8") (pinfunction "GND_29_8") (pintype "power_in"))
      (node (ref "U2") (pin "29_9") (pinfunction "GND_29_9") (pintype "power_in"))
      (node (ref "U3") (pin "13") (pinfunction "GND_13") (pintype "power_in"))
      (node (ref "U4") (pin "1") (pinfunction "CTG_1") (pintype "power_in"))
      (node (ref "U4") (pin "4") (pinfunction "GND_4") (pintype "power_in"))
      (node (ref "U4") (pin "6") (pinfunction "QSTRT_6") (pintype "input"))
      (node (ref "U4") (pin "9") (pinfunction "EP_9") (pintype "power_in"))
    )
    (net (code "14") (name "GPIO8") (class "Default")
      (node (ref "R1") (pin "2") (pinfunction "2_2") (pintype "passive"))
      (node (ref "U2") (pin "10") (pinfunction "IO8_10") (pintype "bidirectional"))
    )
    (net (code "15") (name "I2C_PW") (class "Default")
      (node (ref "C1") (pin "1") (pinfunction "1_1") (pintype "passive"))
      (node (ref "C2") (pin "1") (pinfunction "1_1") (pintype "passive"))
      (node (ref "R1-PINH") (pin "2") (pinfunction "2_2") (pintype "passive"))
      (node (ref "R2-PINH") (pin "2") (pinfunction "2_2") (pintype "passive"))
      (node (ref "SENSOR2") (pin "2") (pinfunction "CSB_2") (pintype "input"))
      (node (ref "SENSOR2") (pin "6") (pinfunction "VDDIO_6") (pintype "power_in"))
      (node (ref "SENSOR2") (pin "8") (pinfunction "VDD_8") (pintype "power_in"))
      (node (ref "U2") (pin "17") (pinfunction "IO19_17") (pintype "bidirectional"))
    )
    (net (code "16") (name "INT_RTC") (class "Default")
      (node (ref "R1-PINH1") (pin "1") (pinfunction "1_1") (pintype "passive"))
      (node (ref "TP15") (pin "TP") (pinfunction "TP_TP") (pintype "input"))
      (node (ref "U2") (pin "8") (pinfunction "IO0_8") (pintype "bidirectional"))
      (node (ref "U3") (pin "3") (pinfunction "SQW/~{INT}_3") (pintype "output"))
    )
    (net (code "17") (name "IO{slash}BOOT") (class "Default")
      (node (ref "BOOT_BUTTON") (pin "3") (pinfunction "3_3") (pintype "passive"))
      (node (ref "BOOT_BUTTON") (pin "4") (pinfunction "4_4") (pintype "passive"))
      (node (ref "C6") (pin "1") (pinfunction "1_1") (pintype "passive"))
      (node (ref "R_BOOT") (pin "2") (pinfunction "2_2") (pintype "passive"))
      (node (ref "U2") (pin "15") (pinfunction "IO9_15") (pintype "bidirectional"))
    )
    (net (code "18") (name "IO{slash}CHANGE") (class "Default")
      (node (ref "C10") (pin "1") (pinfunction "1_1") (pintype "passive"))
      (node (ref "CHANGE_BUTTON") (pin "3") (pinfunction "3_3") (pintype "passive"))
      (node (ref "CHANGE_BUTTON") (pin "4") (pinfunction "4_4") (pintype "passive"))
      (node (ref "R_CHANGE") (pin "2") (pinfunction "2_2") (pintype "passive"))
      (node (ref "U2") (pin "23") (pinfunction "IO15_23") (pintype "bidirectional"))
    )
    (net (code "19") (name "MISO") (class "Default")
      (node (ref "D12") (pin "2") (pinfunction "2_2") (pintype "passive"))
      (node (ref "J1") (pin "P7") (pinfunction "DAT0_P7") (pintype "bidirectional"))
      (node (ref "R8") (pin "1") (pinfunction "1_1") (pintype "passive"))
      (node (ref "TP6") (pin "TP") (pinfunction "TP_TP") (pintype "input"))
      (node (ref "U1") (pin "2") (pinfunction "DO(IO1)_2") (pintype "bidirectional"))
      (node (ref "U2") (pin "27") (pinfunction "IO2_27") (pintype "bidirectional"))
    )
    (net (code "20") (name "MOSI") (class "Default")
      (node (ref "D11") (pin "2") (pinfunction "2_2") (pintype "passive"))
      (node (ref "J1") (pin "P3") (pinfunction "CMD_P3") (pintype "bidirectional"))
      (node (ref "J4") (pin "14") (pinfunction "14_14") (pintype "bidirectional"))
      (node (ref "R7") (pin "1") (pinfunction "1_1") (pintype "passive"))
      (node (ref "TP7") (pin "TP") (pinfunction "TP_TP") (pintype "input"))
      (node (ref "U1") (pin "5") (pinfunction "DI(IO0)_5") (pintype "bidirectional"))
      (node (ref "U2") (pin "7") (pinfunction "IO7_7") (pintype "bidirectional"))
    )
    (net (code "21") (name "Net-(CHG_LED-PadC)") (class "Default")
      (node (ref "CHG_LED") (pin "C") (pinfunction "C_C") (pintype "passive"))
      (node (ref "R1_BAT") (pin "2") (pinfunction "2_2") (pintype "passive"))
    )
    (net (code "22") (name "Net-(D2-CATHODE)") (class "Default")
      (node (ref "C1_BAT1") (pin "1") (pinfunction "1_1") (pintype "passive"))
      (node (ref "D2") (pin "1") (pinfunction "CATHODE_1") (pintype "bidirectional"))
      (node (ref "IC4") (pin "1") (pinfunction "VIN_1") (pintype "bidirectional"))
      (node (ref "IC4") (pin "3") (pinfunction "CE_3") (pintype "bidirectional"))
      (node (ref "Q1") (pin "2") (pinfunction "S_2") (pintype "bidirectional"))
    )
    (net (code "23") (name "Net-(D3-A)") (class "Default")
      (node (ref "C4") (pin "1") (pinfunction "1_1") (pintype "passive"))
      (node (ref "D3") (pin "2") (pinfunction "A_2") (pintype "bidirectional"))
      (node (ref "D4") (pin "1") (pinfunction "K_1") (pintype "bidirectional"))
    )
    (net (code "24") (name "Net-(D7-CATHODE)") (class "Default")
      (node (ref "D7") (pin "1") (pinfunction "CATHODE_1") (pintype "bidirectional"))
      (node (ref "R_CAPACITOR") (pin "2") (pinfunction "2_2") (pintype "passive"))
    )
    (net (code "25") (name "Net-(EPD_C1-Pad1)") (class "Default")
      (node (ref "EPD_C1") (pin "1") (pinfunction "1_1") (pintype "passive"))
      (node (ref "J4") (pin "4") (pinfunction "4_4") (pintype "bidirectional"))
    )
    (net (code "26") (name "Net-(EPD_C2-Pad1)") (class "Default")
      (node (ref "EPD_C2") (pin "1") (pinfunction "1_1") (pintype "passive"))
      (node (ref "J4") (pin "5") (pinfunction "5_5") (pintype "bidirectional"))
    )
    (net (code "27") (name "Net-(EPD_C6-Pad1)") (class "Default")
      (node (ref "EPD_C6") (pin "1") (pinfunction "1_1") (pintype "passive"))
      (node (ref "J4") (pin "18") (pinfunction "18_18") (pintype "bidirectional"))
    )
    (net (code "28") (name "Net-(EPD_C7-Pad1)") (class "Default")
      (node (ref "EPD_C7") (pin "1") (pinfunction "1_1") (pintype "passive"))
      (node (ref "J4") (pin "19") (pinfunction "19_19") (pintype "bidirectional"))
    )
    (net (code "29") (name "Net-(EPD_C8-Pad1)") (class "Default")
      (node (ref "EPD_C8") (pin "1") (pinfunction "1_1") (pintype "passive"))
      (node (ref "J4") (pin "20") (pinfunction "20_20") (pintype "bidirectional"))
    )
    (net (code "30") (name "Net-(EPD_C10-Pad1)") (class "Default")
      (node (ref "EPD_C10") (pin "1") (pinfunction "1_1") (pintype "passive"))
      (node (ref "J4") (pin "22") (pinfunction "22_22") (pintype "bidirectional"))
    )
    (net (code "31") (name "Net-(EPD_C12-Pad1)") (class "Default")
      (node (ref "EPD_C12") (pin "1") (pinfunction "1_1") (pintype "passive"))
      (node (ref "J4") (pin "24") (pinfunction "24_24") (pintype "bidirectional"))
    )
    (net (code "32") (name "Net-(IC1-CT)") (class "Default")
      (node (ref "C_DELAY") (pin "1") (pinfunction "1_1") (pintype "passive"))
      (node (ref "IC1") (pin "5") (pinfunction "CT_5") (pintype "bidirectional"))
    )
    (net (code "33") (name "Net-(J2-PadA5)") (class "Default")
      (node (ref "J2") (pin "A5") (pinfunction "A5_A5") (pintype "bidirectional"))
      (node (ref "R2-USB1") (pin "2") (pinfunction "2_2") (pintype "passive"))
    )
    (net (code "34") (name "Net-(J2-PadB5)") (class "Default")
      (node (ref "J2") (pin "B5") (pinfunction "B5_B5") (pintype "bidirectional"))
      (node (ref "R2-USB") (pin "1") (pinfunction "1_1") (pintype "passive"))
    )
    (net (code "35") (name "Net-(MCP73831-PROG)") (class "Default")
      (node (ref "MCP73831") (pin "5") (pinfunction "PROG_5") (pintype "input"))
      (node (ref "R2_BAT") (pin "2") (pinfunction "2_2") (pintype "passive"))
    )
    (net (code "36") (name "Net-(MCP73831-STAT)") (class "Default")
      (node (ref "MCP73831") (pin "1") (pinfunction "STAT_1") (pintype "output"))
      (node (ref "R1_BAT") (pin "1") (pinfunction "1_1") (pintype "passive"))
    )
    (net (code "37") (name "PREVGH") (class "Default")
      (node (ref "D5") (pin "1") (pinfunction "K_1") (pintype "bidirectional"))
      (node (ref "EPD_C9") (pin "1") (pinfunction "1_1") (pintype "passive"))
      (node (ref "J4") (pin "21") (pinfunction "21_21") (pintype "bidirectional"))
    )
    (net (code "38") (name "PREVGL") (class "Default")
      (node (ref "D4") (pin "2") (pinfunction "A_2") (pintype "bidirectional"))
      (node (ref "EPD_C11") (pin "1") (pinfunction "1_1") (pintype "passive"))
      (node (ref "J4") (pin "23") (pinfunction "23_23") (pintype "bidirectional"))
    )
    (net (code "39") (name "RESE") (class "Default")
      (node (ref "J4") (pin "3") (pinfunction "3_3") (pintype "bidirectional"))
      (node (ref "Q3") (pin "2") (pinfunction "S_2") (pintype "bidirectional"))
      (node (ref "R3") (pin "2") (pinfunction "2_2") (pintype "passive"))
    )
    (net (code "40") (name "RESE'") (class "Default")
      (node (ref "R2") (pin "2") (pinfunction "2_2") (pintype "passive"))
      (node (ref "R3") (pin "1") (pinfunction "1_1") (pintype "passive"))
      (node (ref "SJ1") (pin "2") (pinfunction "2_2") (pintype "passive"))
    )
    (net (code "41") (name "RESET") (class "Default")
      (node (ref "C5") (pin "1") (pinfunction "1_1") (pintype "passive"))
      (node (ref "IC1") (pin "1") (pinfunction "VOUT_1") (pintype "bidirectional"))
      (node (ref "RESET_BUTTON") (pin "3") (pinfunction "3_3") (pintype "passive"))
      (node (ref "RESET_BUTTON") (pin "4") (pinfunction "4_4") (pintype "passive"))
      (node (ref "R_RESET") (pin "2") (pinfunction "2_2") (pintype "passive"))
      (node (ref "U2") (pin "3") (pinfunction "EN_3") (pintype "input"))
    )
    (net (code "42") (name "RTC_RST") (class "Default")
      (node (ref "U2") (pin "16") (pinfunction "IO18_16") (pintype "bidirectional"))
      (node (ref "U3") (pin "4") (pinfunction "~{RST}_4") (pintype "input"))
    )
    (net (code "43") (name "RX") (class "Default")
      (node (ref "TP2") (pin "TP") (pinfunction "TP_TP") (pintype "input"))
      (node (ref "U2") (pin "24") (pinfunction "RXD0/GPIO17_24") (pintype "bidirectional"))
    )
    (net (code "44") (name "SCK") (class "Default")
      (node (ref "D10") (pin "2") (pinfunction "2_2") (pintype "passive"))
      (node (ref "J1") (pin "P5") (pinfunction "CLK_P5") (pintype "bidirectional"))
      (node (ref "J4") (pin "13") (pinfunction "13_13") (pintype "bidirectional"))
      (node (ref "R6") (pin "1") (pinfunction "1_1") (pintype "passive"))
      (node (ref "TP8") (pin "TP") (pinfunction "TP_TP") (pintype "input"))
      (node (ref "U1") (pin "6") (pinfunction "CLK_6") (pintype "input"))
      (node (ref "U2") (pin "6") (pinfunction "IO6_6") (pintype "bidirectional"))
    )
    (net (code "45") (name "SCL") (class "Default")
      (node (ref "J3") (pin "4") (pinfunction "4_4") (pintype "passive"))
      (node (ref "R2-PINH") (pin "1") (pinfunction "1_1") (pintype "passive"))
      (node (ref "SENSOR2") (pin "4") (pinfunction "SCK_4") (pintype "input"))
      (node (ref "U2") (pin "20") (pinfunction "IO22_20") (pintype "bidirectional"))
      (node (ref "U3") (pin "16") (pinfunction "SCL_16") (pintype "input"))
      (node (ref "U4") (pin "7") (pinfunction "SCL_7") (pintype "input"))
    )
    (net (code "46") (name "SDA") (class "Default")
      (node (ref "J3") (pin "3") (pinfunction "3_3") (pintype "passive"))
      (node (ref "R1-PINH") (pin "1") (pinfunction "1_1") (pintype "passive"))
      (node (ref "SENSOR2") (pin "3") (pinfunction "SDI_3") (pintype "bidirectional"))
      (node (ref "U2") (pin "19") (pinfunction "IO21_19") (pintype "bidirectional"))
      (node (ref "U3") (pin "15") (pinfunction "SDA_15") (pintype "bidirectional"))
      (node (ref "U4") (pin "8") (pinfunction "SDA_8") (pintype "bidirectional"))
    )
    (net (code "47") (name "SRC") (class "Default")
      (node (ref "C4") (pin "2") (pinfunction "2_2") (pintype "passive"))
      (node (ref "D5") (pin "2") (pinfunction "A_2") (pintype "bidirectional"))
      (node (ref "L1") (pin "1") (pinfunction "1_1") (pintype "passive"))
      (node (ref "Q3") (pin "3") (pinfunction "D_3") (pintype "bidirectional"))
    )
    (net (code "48") (name "SS_SD") (class "Default")
      (node (ref "D8") (pin "2") (pinfunction "2_2") (pintype "passive"))
      (node (ref "J1") (pin "P2") (pinfunction "CD/DAT3_P2") (pintype "bidirectional"))
      (node (ref "R10") (pin "1") (pinfunction "1_1") (pintype "passive"))
      (node (ref "U2") (pin "4") (pinfunction "IO4_4") (pintype "bidirectional"))
    )
    (net (code "49") (name "TX") (class "Default")
      (node (ref "TP1") (pin "TP") (pinfunction "TP_TP") (pintype "input"))
      (node (ref "U2") (pin "25") (pinfunction "TXD0/GPIO16_25") (pintype "bidirectional"))
    )
    (net (code "50") (name "USB_D+") (class "Default")
      (node (ref "D1") (pin "1") (pinfunction "I/O1_1_1") (pintype "bidirectional"))
      (node (ref "U2") (pin "14") (pinfunction "IO13_14") (pintype "bidirectional"))
    )
    (net (code "51") (name "USB_D-") (class "Default")
      (node (ref "D1") (pin "3") (pinfunction "I/O2_1_3") (pintype "bidirectional"))
      (node (ref "U2") (pin "13") (pinfunction "IO12_13") (pintype "bidirectional"))
    )
    (net (code "52") (name "VBAT") (class "Default")
      (node (ref "C2_BAT") (pin "1") (pinfunction "1_1") (pintype "passive"))
      (node (ref "MCP73831") (pin "3") (pinfunction "VBAT_3") (pintype "power_in"))
      (node (ref "Q1") (pin "3") (pinfunction "D_3") (pintype "bidirectional"))
      (node (ref "TP3") (pin "TP") (pinfunction "TP_TP") (pintype "input"))
      (node (ref "U4") (pin "2") (pinfunction "CELL_2") (pintype "power_in"))
      (node (ref "U4") (pin "3") (pinfunction "VDD_3") (pintype "power_in"))
    )
    (net (code "53") (name "VBUS") (class "Default")
      (node (ref "C1_BAT") (pin "1") (pinfunction "1_1") (pintype "passive"))
      (node (ref "C4_USB") (pin "1") (pinfunction "1_1") (pintype "passive"))
      (node (ref "C5_USB") (pin "1") (pinfunction "1_1") (pintype "passive"))
      (node (ref "CHG_LED") (pin "A") (pinfunction "A_A") (pintype "passive"))
      (node (ref "D1") (pin "5") (pinfunction "VBUS_5") (pintype "bidirectional"))
      (node (ref "D2") (pin "2") (pinfunction "ANODE_2") (pintype "bidirectional"))
      (node (ref "MCP73831") (pin "4") (pinfunction "VIN_4") (pintype "power_in"))
      (node (ref "PFMF.050.1") (pin "2") (pinfunction "2_2") (pintype "passive"))
      (node (ref "Q1") (pin "1") (pinfunction "G_1") (pintype "bidirectional"))
      (node (ref "R1_PWRUSB") (pin "2") (pinfunction "2_2") (pintype "passive"))
      (node (ref "TP14") (pin "TP") (pinfunction "TP_TP") (pintype "input"))
    )
    (net (code "54") (name "VRTC") (class "Default")
      (node (ref "C10_SUPERCAP") (pin "2") (pinfunction "2_2") (pintype "passive"))
      (node (ref "C8") (pin "1") (pinfunction "1_1") (pintype "passive"))
      (node (ref "R_CAPACITOR") (pin "1") (pinfunction "1_1") (pintype "passive"))
      (node (ref "U3") (pin "14") (pinfunction "VBAT_14") (pintype "power_in"))
    )
    (net (code "55") (name "VUSB") (class "Default")
      (node (ref "J2") (pin "A4") (pinfunction "A4_A4") (pintype "bidirectional"))
      (node (ref "J2") (pin "A9") (pinfunction "A9_A9") (pintype "bidirectional"))
      (node (ref "J2") (pin "B4") (pinfunction "B4_B4") (pintype "bidirectional"))
      (node (ref "J2") (pin "B9") (pinfunction "B9_B9") (pintype "bidirectional"))
      (node (ref "PFMF.050.1") (pin "1") (pinfunction "1_1") (pintype "passive"))
    )
    (net (code "56") (name "unconnected-(IC1-NC-Pad4)") (class "Default")
      (node (ref "IC1") (pin "4") (pinfunction "NC_4") (pintype "no_connect"))
    )
    (net (code "57") (name "unconnected-(IC4-NC-Pad4)") (class "Default")
      (node (ref "IC4") (pin "4") (pinfunction "NC_4") (pintype "no_connect"))
    )
    (net (code "58") (name "unconnected-(J1-DAT1-PadP8)") (class "Default")
      (node (ref "J1") (pin "P8") (pinfunction "DAT1_P8") (pintype "bidirectional"))
    )
    (net (code "59") (name "unconnected-(J1-DAT2-PadP1)") (class "Default")
      (node (ref "J1") (pin "P1") (pinfunction "DAT2_P1") (pintype "bidirectional"))
    )
    (net (code "60") (name "unconnected-(J1-DETECTION_1-PadS1)") (class "Default")
      (node (ref "J1") (pin "S1") (pinfunction "DETECTION_1_S1") (pintype "bidirectional"))
    )
    (net (code "61") (name "unconnected-(J1-DETECTION_2-PadS2)") (class "Default")
      (node (ref "J1") (pin "S2") (pinfunction "DETECTION_2_S2") (pintype "bidirectional"))
    )
    (net (code "62") (name "unconnected-(J2-PadA8)") (class "Default")
      (node (ref "J2") (pin "A8") (pinfunction "A8_A8") (pintype "bidirectional"))
    )
    (net (code "63") (name "unconnected-(J2-PadB8)") (class "Default")
      (node (ref "J2") (pin "B8") (pinfunction "B8_B8") (pintype "bidirectional"))
    )
    (net (code "64") (name "unconnected-(J4-Pad1)") (class "Default")
      (node (ref "J4") (pin "1") (pinfunction "1_1") (pintype "bidirectional"))
    )
    (net (code "65") (name "unconnected-(J4-Pad6)") (class "Default")
      (node (ref "J4") (pin "6") (pinfunction "6_6") (pintype "bidirectional"))
    )
    (net (code "66") (name "unconnected-(J4-Pad7)") (class "Default")
      (node (ref "J4") (pin "7") (pinfunction "7_7") (pintype "bidirectional"))
    )
    (net (code "67") (name "unconnected-(U2-NC-Pad22)") (class "Default")
      (node (ref "U2") (pin "22") (pinfunction "NC_22") (pintype "no_connect"))
    )
    (net (code "68") (name "unconnected-(U4-~{ALERT}-Pad5)") (class "Default")
      (node (ref "U4") (pin "5") (pinfunction "~{ALERT}_5") (pintype "output"))
    )
  )
)
